# Top.net
KiCad netlist of a schematic drawn in Altium Designer
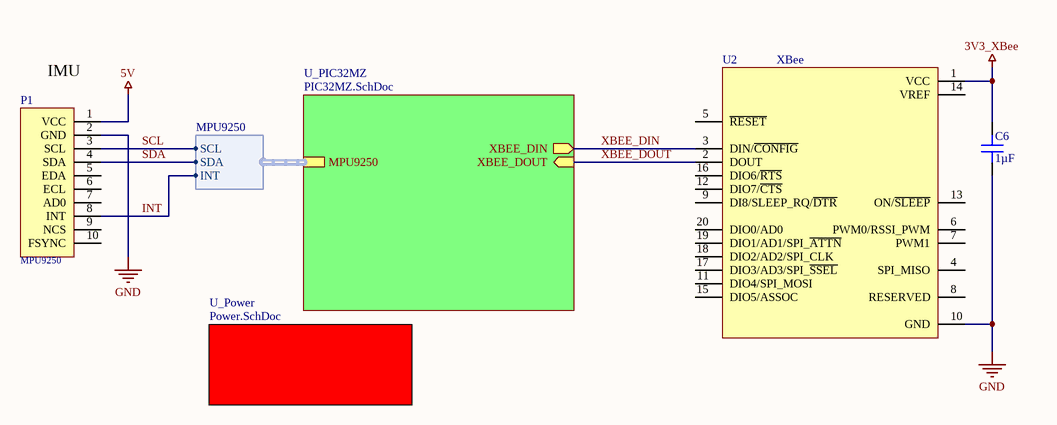
[diagram p0: Top.SchDoc]

(export (version "E")
  (design (tool "Eeschema 10.0.6"))
  (components
    (comp (ref "C6")
      (value "1µF")
      (footprint "CAP 0603_1608")
      (description "CAP CER 1UF 25V X7R 0603")
      (fields
        (field (name "PART NUMBER") "GCJ188R71E105KA01D")
        (field (name "MANUFACTURER") "Murata Electronics")
      )
      (libsource (lib "Celestial Altium Library - altium_library") (part "Capacitor"))
    )
    (comp (ref "P1")
      (value "MPU9250")
      (footprint "MPU 9150 - 10 pin 0.1\"")
      (description "9 DOF - MPU025- Breakout")
      (fields
        (field (name "MANUFACTURER PART NUMBER") "61301011121")
        (field (name "MANUFACTURER") "Wurth Elektronik")
      )
      (libsource (lib "IC") (part "9 DOF - MPU025 - Breakout"))
    )
    (comp (ref "U2")
      (value "XBee")
      (footprint "XBee")
      (description "802.15.4 Transceiver Module 2.4GHz Antenna Not Included, U.FL Through Hole")
      (libsource (lib "IC") (part "XBee"))
    )
  )
  (nets
    (net (code "2") (name "/INT") (class "Default")
      (node (ref "P1") (pin "8") (pinfunction "INT_8") (pintype "passive"))
    )
    (net (code "3") (name "/SCL") (class "Default")
      (node (ref "P1") (pin "3") (pinfunction "SCL_3") (pintype "passive"))
    )
    (net (code "4") (name "/SDA") (class "Default")
      (node (ref "P1") (pin "4") (pinfunction "SDA_4") (pintype "passive"))
    )
    (net (code "5") (name "/XBEE_DIN") (class "Default")
      (node (ref "U2") (pin "3") (pinfunction "DIN/~{CONFIG}_3") (pintype "passive"))
    )
    (net (code "6") (name "/XBEE_DOUT") (class "Default")
      (node (ref "U2") (pin "2") (pinfunction "DOUT_2") (pintype "passive"))
    )
    (net (code "8") (name "3V3_XBee") (class "Default")
      (node (ref "C6") (pin "2") (pinfunction "2_2") (pintype "passive"))
      (node (ref "U2") (pin "1") (pinfunction "VCC_1") (pintype "power_in"))
    )
    (net (code "9") (name "5V") (class "Default")
      (node (ref "P1") (pin "1") (pinfunction "VCC_1") (pintype "passive"))
    )
    (net (code "10") (name "GND") (class "Default")
      (node (ref "C6") (pin "1") (pinfunction "1_1") (pintype "passive"))
      (node (ref "P1") (pin "2") (pinfunction "GND_2") (pintype "passive"))
      (node (ref "U2") (pin "10") (pinfunction "GND_10") (pintype "power_in"))
    )
    (net (code "11") (name "unconnected-(P1-AD0-Pad7)") (class "Default")
      (node (ref "P1") (pin "7") (pinfunction "AD0_7") (pintype "passive"))
    )
    (net (code "12") (name "unconnected-(P1-ECL-Pad6)") (class "Default")
      (node (ref "P1") (pin "6") (pinfunction "ECL_6") (pintype "passive"))
    )
    (net (code "13") (name "unconnected-(P1-EDA-Pad5)") (class "Default")
      (node (ref "P1") (pin "5") (pinfunction "EDA_5") (pintype "passive"))
    )
    (net (code "14") (name "unconnected-(P1-FSYNC-Pad10)") (class "Default")
      (node (ref "P1") (pin "10") (pinfunction "FSYNC_10") (pintype "passive"))
    )
    (net (code "15") (name "unconnected-(P1-NCS-Pad9)") (class "Default")
      (node (ref "P1") (pin "9") (pinfunction "NCS_9") (pintype "passive"))
    )
    (net (code "16") (name "unconnected-(U2-DI8{slash}SLEEP_RQ{slash}~{DTR}-Pad9)") (class "Default")
      (node (ref "U2") (pin "9") (pinfunction "DI8/SLEEP_RQ/~{DTR}_9") (pintype "passive"))
    )
    (net (code "17") (name "unconnected-(U2-DIO0{slash}AD0-Pad20)") (class "Default")
      (node (ref "U2") (pin "20") (pinfunction "DIO0/AD0_20") (pintype "passive"))
    )
    (net (code "18") (name "unconnected-(U2-DIO1{slash}AD1{slash}SPI_~{ATTN}-Pad19)") (class "Default")
      (node (ref "U2") (pin "19") (pinfunction "DIO1/AD1/SPI_~{ATTN}_19") (pintype "passive"))
    )
    (net (code "19") (name "unconnected-(U2-DIO2{slash}AD2{slash}SPI_CLK-Pad18)") (class "Default")
      (node (ref "U2") (pin "18") (pinfunction "DIO2/AD2/SPI_CLK_18") (pintype "passive"))
    )
    (net (code "20") (name "unconnected-(U2-DIO3{slash}AD3{slash}SPI_~{SSEL}-Pad17)") (class "Default")
      (node (ref "U2") (pin "17") (pinfunction "DIO3/AD3/SPI_~{SSEL}_17") (pintype "passive"))
    )
    (net (code "21") (name "unconnected-(U2-DIO4{slash}SPI_MOSI-Pad11)") (class "Default")
      (node (ref "U2") (pin "11") (pinfunction "DIO4/SPI_MOSI_11") (pintype "passive"))
    )
    (net (code "22") (name "unconnected-(U2-DIO5{slash}ASSOC-Pad15)") (class "Default")
      (node (ref "U2") (pin "15") (pinfunction "DIO5/ASSOC_15") (pintype "passive"))
    )
    (net (code "23") (name "unconnected-(U2-DIO6{slash}~{RTS}-Pad16)") (class "Default")
      (node (ref "U2") (pin "16") (pinfunction "DIO6/~{RTS}_16") (pintype "passive"))
    )
    (net (code "24") (name "unconnected-(U2-DIO7{slash}~{CTS}-Pad12)") (class "Default")
      (node (ref "U2") (pin "12") (pinfunction "DIO7/~{CTS}_12") (pintype "passive"))
    )
    (net (code "25") (name "unconnected-(U2-ON{slash}~{SLEEP}-Pad13)") (class "Default")
      (node (ref "U2") (pin "13") (pinfunction "ON/~{SLEEP}_13") (pintype "passive"))
    )
    (net (code "26") (name "unconnected-(U2-PWM0{slash}RSSI_PWM-Pad6)") (class "Default")
      (node (ref "U2") (pin "6") (pinfunction "PWM0/RSSI_PWM_6") (pintype "passive"))
    )
    (net (code "27") (name "unconnected-(U2-PWM1-Pad7)") (class "Default")
      (node (ref "U2") (pin "7") (pinfunction "PWM1_7") (pintype "passive"))
    )
    (net (code "28") (name "unconnected-(U2-RESERVED-Pad8)") (class "Default")
      (node (ref "U2") (pin "8") (pinfunction "RESERVED_8") (pintype "passive"))
    )
    (net (code "29") (name "unconnected-(U2-SPI_MISO-Pad4)") (class "Default")
      (node (ref "U2") (pin "4") (pinfunction "SPI_MISO_4") (pintype "passive"))
    )
    (net (code "30") (name "unconnected-(U2-VREF-Pad14)") (class "Default")
      (node (ref "U2") (pin "14") (pinfunction "VREF_14") (pintype "power_in"))
    )
    (net (code "31") (name "unconnected-(U2-~{RESET}-Pad5)") (class "Default")
      (node (ref "U2") (pin "5") (pinfunction "~{RESET}_5") (pintype "passive"))
    )
  )
)
